# Maduino_Zero_A9G_GPS_Tracker_v3_3.net
KiCad netlist of a schematic drawn in EAGLE
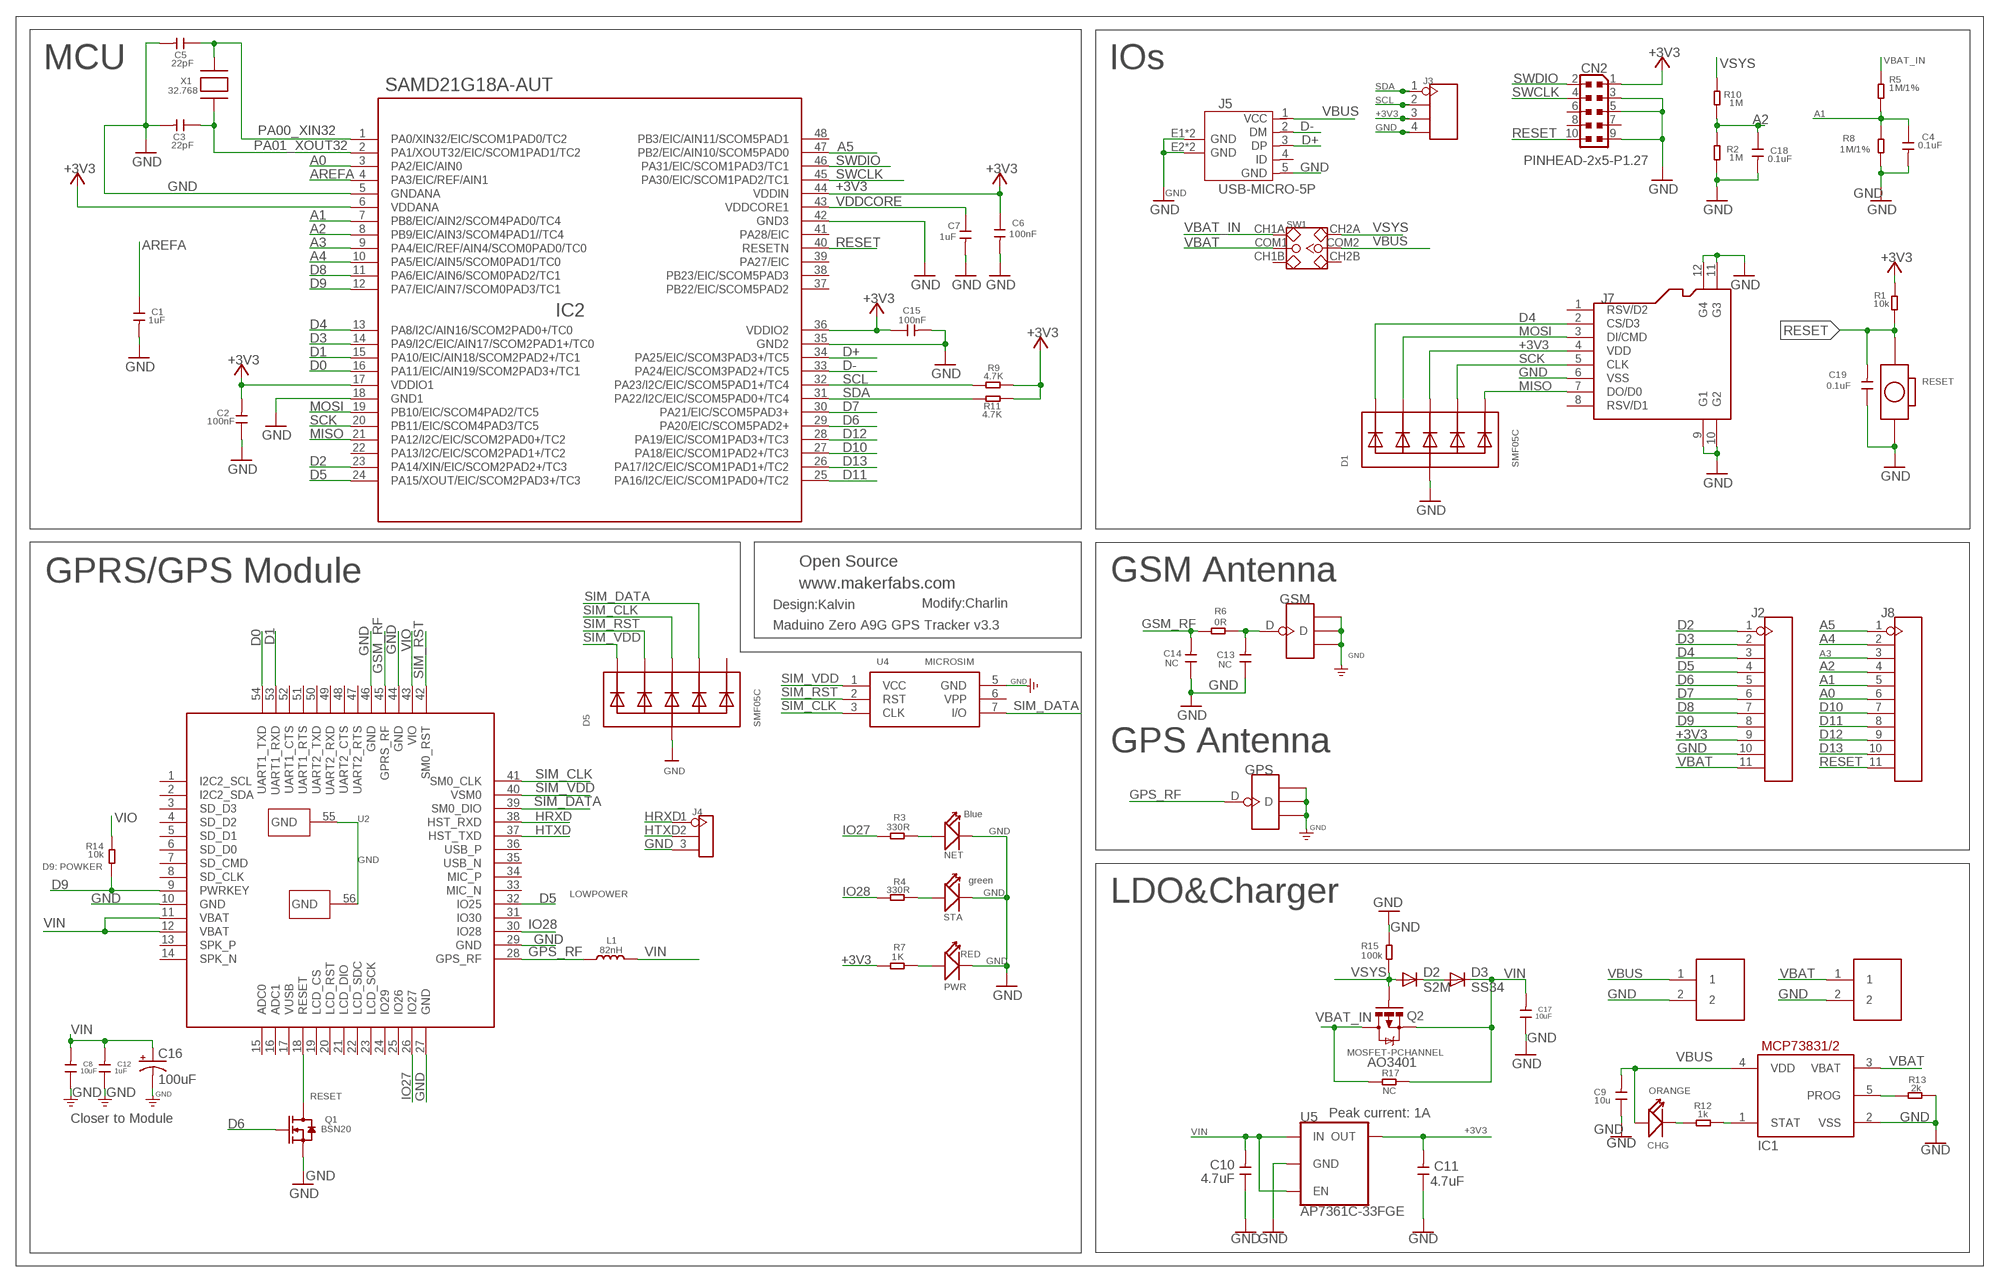
[diagram p0: schematic, sheet 1]

(export (version "E")
  (design (tool "Eeschema 10.0.6"))
  (components
    (comp (ref "C1")
      (value "1uF")
      (footprint "eagle-import:C0603")
      (libsource (lib "eagle-import") (part "C-0603"))
    )
    (comp (ref "C2")
      (value "100nF")
      (footprint "eagle-import:C0603")
      (libsource (lib "eagle-import") (part "C-0603"))
    )
    (comp (ref "C3")
      (value "22pF")
      (footprint "eagle-import:C0603")
      (libsource (lib "eagle-import") (part "C-0603"))
    )
    (comp (ref "C4")
      (value "0.1uF")
      (footprint "eagle-import:C0603")
      (libsource (lib "eagle-import") (part "C-0603"))
    )
    (comp (ref "C5")
      (value "22pF")
      (footprint "eagle-import:C0603")
      (libsource (lib "eagle-import") (part "C-0603"))
    )
    (comp (ref "C6")
      (value "100nF")
      (footprint "eagle-import:C0603")
      (libsource (lib "eagle-import") (part "C-0603"))
    )
    (comp (ref "C7")
      (value "1uF")
      (footprint "eagle-import:C0603")
      (libsource (lib "eagle-import") (part "C-0603"))
    )
    (comp (ref "C8")
      (value "10uF")
      (footprint "eagle-import:C0603")
      (libsource (lib "eagle-import") (part "C-0603"))
    )
    (comp (ref "C9")
      (value "10u")
      (footprint "eagle-import:C0603")
      (libsource (lib "eagle-import") (part "C-0603"))
    )
    (comp (ref "C10")
      (value "4.7uF")
      (footprint "eagle-import:C0603")
      (libsource (lib "eagle-import") (part "C-0603"))
    )
    (comp (ref "C11")
      (value "4.7uF")
      (footprint "eagle-import:C0603")
      (libsource (lib "eagle-import") (part "C-0603"))
    )
    (comp (ref "C12")
      (value "1uF")
      (footprint "eagle-import:C0603")
      (libsource (lib "eagle-import") (part "C-0603"))
    )
    (comp (ref "C13")
      (value "NC")
      (footprint "eagle-import:C0402")
      (libsource (lib "eagle-import") (part "C-0402"))
    )
    (comp (ref "C14")
      (value "NC")
      (footprint "eagle-import:C0402")
      (libsource (lib "eagle-import") (part "C-0402"))
    )
    (comp (ref "C15")
      (value "100nF")
      (footprint "eagle-import:C0603")
      (libsource (lib "eagle-import") (part "C-0603"))
    )
    (comp (ref "C16")
      (value "100uF")
      (footprint "eagle-import:EIA3528")
      (libsource (lib "eagle-import") (part "68UF-POLAR-EIA3528-10V-10%(TANT)"))
    )
    (comp (ref "C17")
      (value "10uF")
      (footprint "eagle-import:C0603")
      (libsource (lib "eagle-import") (part "C-0603"))
    )
    (comp (ref "C18")
      (value "0.1uF")
      (footprint "eagle-import:C0603")
      (libsource (lib "eagle-import") (part "C-0603"))
    )
    (comp (ref "C19")
      (value "0.1uF")
      (footprint "eagle-import:C0603")
      (libsource (lib "eagle-import") (part "C-0603"))
    )
    (comp (ref "CHG")
      (value "ORANGE")
      (footprint "eagle-import:D0603")
      (libsource (lib "eagle-import") (part "007-LED0603"))
    )
    (comp (ref "CN2")
      (value "PINHEAD-2x5-P1.27")
      (footprint "eagle-import:PINHEAD_2X05_127")
      (libsource (lib "eagle-import") (part "0171_PH127-205DF055G00AROUND-PADS"))
    )
    (comp (ref "D1")
      (value "SMF05C")
      (footprint "eagle-import:SOT363")
      (libsource (lib "eagle-import") (part "TVSARRAY_5LANE"))
    )
    (comp (ref "D2")
      (value "S2M")
      (footprint "eagle-import:DO-214AC")
      (libsource (lib "eagle-import") (part "DIODE-DO-214AC"))
    )
    (comp (ref "D3")
      (value "SS34")
      (footprint "eagle-import:DO-214AC")
      (libsource (lib "eagle-import") (part "DIODE-DO-214AC"))
    )
    (comp (ref "D5")
      (value "SMF05C")
      (footprint "eagle-import:SOT363")
      (libsource (lib "eagle-import") (part "TVSARRAY_5LANE"))
    )
    (comp (ref "GPS")
      (value "ANTENNA-U-FL")
      (footprint "eagle-import:4P-U-FL")
      (libsource (lib "eagle-import") (part "ANTENNA-U-FL"))
    )
    (comp (ref "GSM")
      (value "ANTENNA-U-FL")
      (footprint "eagle-import:4P-U-FL")
      (libsource (lib "eagle-import") (part "ANTENNA-U-FL"))
    )
    (comp (ref "IC1")
      (value "MCP73831/OT")
      (footprint "eagle-import:SOT23-5L")
      (libsource (lib "eagle-import") (part "MCP73831/OT"))
    )
    (comp (ref "IC2")
      (value "SAMD21G18A-AUT")
      (footprint "eagle-import:TQFP48-7X7")
      (libsource (lib "eagle-import") (part "ATSAMD21G18A-AUT"))
    )
    (comp (ref "J1")
      (value "PH2.0-2P-90-DIP")
      (footprint "eagle-import:PH2.0-2P-90-DIP")
      (libsource (lib "eagle-import") (part "PH2.0-2P-90-DIP"))
    )
    (comp (ref "J2")
      (value "HEADER-11P-2.54")
      (footprint "eagle-import:11P-2.54")
      (libsource (lib "eagle-import") (part "HEADER-11P-2.54"))
    )
    (comp (ref "J3")
      (value "HEADER-4P-60/35MILROUND")
      (footprint "eagle-import:4P-65_35ROUND")
      (libsource (lib "eagle-import") (part "HEADER-4P-60/35MILROUND"))
    )
    (comp (ref "J4")
      (value "HEADER-3P-2.54")
      (footprint "eagle-import:3P-2.54")
      (libsource (lib "eagle-import") (part "HEADER-3P-2.54"))
    )
    (comp (ref "J5")
      (value "USB-MICRO-5P")
      (footprint "eagle-import:MICRO-USB-5P")
      (libsource (lib "eagle-import") (part "USB-MICRO-5P"))
    )
    (comp (ref "J6")
      (value "PH2.0-2P-90-DIP")
      (footprint "eagle-import:PH2.0-2P-90-DIP")
      (libsource (lib "eagle-import") (part "PH2.0-2P-90-DIP"))
    )
    (comp (ref "J7")
      (value "HOLDER-MICROSD-8P")
      (footprint "eagle-import:8P-SMD")
      (libsource (lib "eagle-import") (part "HOLDER-MICROSD-8P"))
    )
    (comp (ref "J8")
      (value "HEADER-11P-2.54")
      (footprint "eagle-import:11P-2.54")
      (libsource (lib "eagle-import") (part "HEADER-11P-2.54"))
    )
    (comp (ref "L1")
      (value "82nH")
      (footprint "eagle-import:L0603")
      (libsource (lib "eagle-import") (part "L'0603'"))
    )
    (comp (ref "NET")
      (value "Blue")
      (footprint "eagle-import:LED-0603")
      (libsource (lib "eagle-import") (part "LED'0603'"))
    )
    (comp (ref "PWR")
      (value "RED")
      (footprint "eagle-import:LED-0603")
      (libsource (lib "eagle-import") (part "LED'0603'"))
    )
    (comp (ref "Q1")
      (value "BSN20")
      (footprint "eagle-import:SOT23@1")
      (libsource (lib "eagle-import") (part "MOSFET-N'SOT23'"))
    )
    (comp (ref "Q2")
      (value "MOSFET-PCHANNEL")
      (footprint "eagle-import:SOT23-3")
      (libsource (lib "eagle-import") (part "MOSFET-PCHANNEL"))
    )
    (comp (ref "R1")
      (value "10k")
      (footprint "eagle-import:R0603")
      (libsource (lib "eagle-import") (part "R-0603"))
    )
    (comp (ref "R2")
      (value "1M")
      (footprint "eagle-import:R0603")
      (libsource (lib "eagle-import") (part "R-0603"))
    )
    (comp (ref "R3")
      (value "330R")
      (footprint "eagle-import:R0603")
      (libsource (lib "eagle-import") (part "R-0603"))
    )
    (comp (ref "R4")
      (value "330R")
      (footprint "eagle-import:R0603")
      (libsource (lib "eagle-import") (part "R-0603"))
    )
    (comp (ref "R5")
      (value "1M/1%")
      (footprint "eagle-import:R0603")
      (libsource (lib "eagle-import") (part "R-0603"))
    )
    (comp (ref "R6")
      (value "0R")
      (footprint "eagle-import:R0603")
      (libsource (lib "eagle-import") (part "R-0603"))
    )
    (comp (ref "R7")
      (value "1K")
      (footprint "eagle-import:R0603")
      (libsource (lib "eagle-import") (part "R-0603"))
    )
    (comp (ref "R8")
      (value "1M/1%")
      (footprint "eagle-import:R0603")
      (libsource (lib "eagle-import") (part "R-0603"))
    )
    (comp (ref "R9")
      (value "4.7K")
      (footprint "eagle-import:R0603")
      (libsource (lib "eagle-import") (part "R-0603"))
    )
    (comp (ref "R10")
      (value "1M")
      (footprint "eagle-import:R0603")
      (libsource (lib "eagle-import") (part "R-0603"))
    )
    (comp (ref "R11")
      (value "4.7K")
      (footprint "eagle-import:R0603")
      (libsource (lib "eagle-import") (part "R-0603"))
    )
    (comp (ref "R12")
      (value "1k")
      (footprint "eagle-import:R0603")
      (libsource (lib "eagle-import") (part "R-0603"))
    )
    (comp (ref "R13")
      (value "2k")
      (footprint "eagle-import:R0603")
      (libsource (lib "eagle-import") (part "R-0603"))
    )
    (comp (ref "R14")
      (value "10k")
      (footprint "eagle-import:R0603")
      (libsource (lib "eagle-import") (part "R-0603"))
    )
    (comp (ref "R15")
      (value "100k")
      (footprint "eagle-import:R0603")
      (libsource (lib "eagle-import") (part "R-0603"))
    )
    (comp (ref "R17")
      (value "NC")
      (footprint "eagle-import:R0603")
      (libsource (lib "eagle-import") (part "R-0603"))
    )
    (comp (ref "RESET")
      (value "BOTTON-2P-90D")
      (footprint "eagle-import:2P-7.62X3.56-90D")
      (libsource (lib "eagle-import") (part "BOTTON-2P-90D"))
    )
    (comp (ref "STA")
      (value "green")
      (footprint "eagle-import:LED-0603")
      (libsource (lib "eagle-import") (part "LED'0603'"))
    )
    (comp (ref "SW1")
      (value "SWITCH-2CH-6P")
      (footprint "eagle-import:6P-2CH-2.54-7.6X3.0")
      (libsource (lib "eagle-import") (part "SWITCH-2CH-6P"))
    )
    (comp (ref "U2")
      (value "A9G")
      (footprint "eagle-import:A9G")
      (libsource (lib "eagle-import") (part "A9G"))
    )
    (comp (ref "U4")
      (value "MICROSIM")
      (footprint "eagle-import:MICROSIM")
      (libsource (lib "eagle-import") (part "MICROSIM"))
    )
    (comp (ref "U5")
      (value "AP7361C-33FGE")
      (footprint "eagle-import:8-UDFN")
      (libsource (lib "eagle-import") (part "AP7361C-33FGE"))
    )
    (comp (ref "X1")
      (value "32.768")
      (footprint "eagle-import:XTAL3215")
      (libsource (lib "eagle-import") (part "XTAL-3.2X1.5"))
    )
  )
  (nets
    (net (code "1") (name "+3V3") (class "Default")
      (node (ref "C11") (pin "2") (pinfunction "2_2") (pintype "passive"))
      (node (ref "C15") (pin "1") (pinfunction "1_1") (pintype "passive"))
      (node (ref "C2") (pin "2") (pinfunction "2_2") (pintype "passive"))
      (node (ref "C6") (pin "1") (pinfunction "1_1") (pintype "passive"))
      (node (ref "CN2") (pin "1") (pinfunction "1_1") (pintype "passive"))
      (node (ref "D1") (pin "4") (pinfunction "C3_4") (pintype "passive"))
      (node (ref "IC2") (pin "17") (pinfunction "VDDIO1_17") (pintype "power_in"))
      (node (ref "IC2") (pin "36") (pinfunction "VDDIO2_36") (pintype "power_in"))
      (node (ref "IC2") (pin "44") (pinfunction "VDDIN_44") (pintype "power_in"))
      (node (ref "IC2") (pin "6") (pinfunction "VDDANA_6") (pintype "power_in"))
      (node (ref "J2") (pin "9") (pinfunction "9_9") (pintype "bidirectional"))
      (node (ref "J3") (pin "3") (pinfunction "P$3_3") (pintype "bidirectional"))
      (node (ref "J7") (pin "4") (pinfunction "VDD_4") (pintype "bidirectional"))
      (node (ref "R1") (pin "2") (pinfunction "2_2") (pintype "passive"))
      (node (ref "R11") (pin "2") (pinfunction "2_2") (pintype "passive"))
      (node (ref "R7") (pin "1") (pinfunction "1_1") (pintype "passive"))
      (node (ref "R9") (pin "2") (pinfunction "2_2") (pintype "passive"))
      (node (ref "U5") (pin "1") (pinfunction "OUT_1") (pintype "output"))
    )
    (net (code "2") (name "/A0") (class "Default")
      (node (ref "IC2") (pin "3") (pinfunction "PA2/EIC/AIN0_3") (pintype "bidirectional"))
      (node (ref "J8") (pin "6") (pinfunction "6_6") (pintype "bidirectional"))
    )
    (net (code "3") (name "/A1") (class "Default")
      (node (ref "C4") (pin "1") (pinfunction "1_1") (pintype "passive"))
      (node (ref "IC2") (pin "7") (pinfunction "PB8/EIC/AIN2/SCOM4PAD0/TC4_7") (pintype "bidirectional"))
      (node (ref "J8") (pin "5") (pinfunction "5_5") (pintype "bidirectional"))
      (node (ref "R5") (pin "1") (pinfunction "1_1") (pintype "passive"))
      (node (ref "R8") (pin "2") (pinfunction "2_2") (pintype "passive"))
    )
    (net (code "4") (name "/A2") (class "Default")
      (node (ref "C18") (pin "1") (pinfunction "1_1") (pintype "passive"))
      (node (ref "IC2") (pin "8") (pinfunction "PB9/EIC/AIN3/SCOM4PAD1//TC4_8") (pintype "bidirectional"))
      (node (ref "J8") (pin "4") (pinfunction "4_4") (pintype "bidirectional"))
      (node (ref "R10") (pin "1") (pinfunction "1_1") (pintype "passive"))
      (node (ref "R2") (pin "2") (pinfunction "2_2") (pintype "passive"))
    )
    (net (code "5") (name "/A3") (class "Default")
      (node (ref "IC2") (pin "9") (pinfunction "PA4/EIC/REF/AIN4/SCOM0PAD0/TC0_9") (pintype "bidirectional"))
      (node (ref "J8") (pin "3") (pinfunction "3_3") (pintype "bidirectional"))
    )
    (net (code "6") (name "/A4") (class "Default")
      (node (ref "IC2") (pin "10") (pinfunction "PA5/EIC/AIN5/SCOM0PAD1/TC0_10") (pintype "bidirectional"))
      (node (ref "J8") (pin "2") (pinfunction "2_2") (pintype "bidirectional"))
    )
    (net (code "7") (name "/A5") (class "Default")
      (node (ref "IC2") (pin "47") (pinfunction "PB2/EIC/AIN10/SCOM5PAD0_47") (pintype "bidirectional"))
      (node (ref "J8") (pin "1") (pinfunction "1_1") (pintype "bidirectional"))
    )
    (net (code "8") (name "/AREFA") (class "Default")
      (node (ref "C1") (pin "1") (pinfunction "1_1") (pintype "passive"))
      (node (ref "IC2") (pin "4") (pinfunction "PA3/EIC/REF/AIN1_4") (pintype "bidirectional"))
    )
    (net (code "9") (name "/D+") (class "Default")
      (node (ref "IC2") (pin "34") (pinfunction "PA25/EIC/SCOM3PAD3+/TC5_34") (pintype "bidirectional"))
      (node (ref "J5") (pin "3") (pinfunction "DP_3") (pintype "bidirectional"))
    )
    (net (code "10") (name "/D-") (class "Default")
      (node (ref "IC2") (pin "33") (pinfunction "PA24/EIC/SCOM3PAD2+/TC5_33") (pintype "bidirectional"))
      (node (ref "J5") (pin "2") (pinfunction "DM_2") (pintype "bidirectional"))
    )
    (net (code "11") (name "/D0") (class "Default")
      (node (ref "IC2") (pin "16") (pinfunction "PA11/EIC/AIN19/SCOM2PAD3+/TC1_16") (pintype "bidirectional"))
      (node (ref "U2") (pin "54") (pinfunction "UART1_TXD_54") (pintype "bidirectional"))
    )
    (net (code "12") (name "/D1") (class "Default")
      (node (ref "IC2") (pin "15") (pinfunction "PA10/EIC/AIN18/SCOM2PAD2+/TC1_15") (pintype "bidirectional"))
      (node (ref "U2") (pin "53") (pinfunction "UART1_RXD_53") (pintype "bidirectional"))
    )
    (net (code "13") (name "/D2") (class "Default")
      (node (ref "IC2") (pin "23") (pinfunction "PA14/XIN/EIC/SCOM2PAD2+/TC3_23") (pintype "bidirectional"))
      (node (ref "J2") (pin "1") (pinfunction "1_1") (pintype "bidirectional"))
    )
    (net (code "14") (name "/D3") (class "Default")
      (node (ref "IC2") (pin "14") (pinfunction "PA9/I2C/EIC/AIN17/SCOM2PAD1+/TC0_14") (pintype "bidirectional"))
      (node (ref "J2") (pin "2") (pinfunction "2_2") (pintype "bidirectional"))
    )
    (net (code "15") (name "/D4") (class "Default")
      (node (ref "D1") (pin "1") (pinfunction "C1_1") (pintype "passive"))
      (node (ref "IC2") (pin "13") (pinfunction "PA8/I2C/AIN16/SCOM2PAD0+/TC0_13") (pintype "bidirectional"))
      (node (ref "J2") (pin "3") (pinfunction "3_3") (pintype "bidirectional"))
      (node (ref "J7") (pin "2") (pinfunction "CS/D3_2") (pintype "bidirectional"))
    )
    (net (code "16") (name "/D5") (class "Default")
      (node (ref "IC2") (pin "24") (pinfunction "PA15/XOUT/EIC/SCOM2PAD3+/TC3_24") (pintype "bidirectional"))
      (node (ref "J2") (pin "4") (pinfunction "4_4") (pintype "bidirectional"))
      (node (ref "U2") (pin "32") (pinfunction "IO25_32") (pintype "bidirectional"))
    )
    (net (code "17") (name "/D6") (class "Default")
      (node (ref "IC2") (pin "29") (pinfunction "PA20/EIC/SCOM5PAD2+_29") (pintype "bidirectional"))
      (node (ref "J2") (pin "5") (pinfunction "5_5") (pintype "bidirectional"))
      (node (ref "Q1") (pin "1") (pinfunction "G_1") (pintype "passive"))
    )
    (net (code "18") (name "/D7") (class "Default")
      (node (ref "IC2") (pin "30") (pinfunction "PA21/EIC/SCOM5PAD3+_30") (pintype "bidirectional"))
      (node (ref "J2") (pin "6") (pinfunction "6_6") (pintype "bidirectional"))
    )
    (net (code "19") (name "/D8") (class "Default")
      (node (ref "IC2") (pin "11") (pinfunction "PA6/EIC/AIN6/SCOM0PAD2/TC1_11") (pintype "bidirectional"))
      (node (ref "J2") (pin "7") (pinfunction "7_7") (pintype "bidirectional"))
    )
    (net (code "20") (name "/D9") (class "Default")
      (node (ref "IC2") (pin "12") (pinfunction "PA7/EIC/AIN7/SCOM0PAD3/TC1_12") (pintype "bidirectional"))
      (node (ref "J2") (pin "8") (pinfunction "8_8") (pintype "bidirectional"))
      (node (ref "R14") (pin "1") (pinfunction "1_1") (pintype "passive"))
      (node (ref "U2") (pin "9") (pinfunction "PWRKEY_9") (pintype "bidirectional"))
    )
    (net (code "21") (name "/D10") (class "Default")
      (node (ref "IC2") (pin "27") (pinfunction "PA18/EIC/SCOM1PAD2+/TC3_27") (pintype "bidirectional"))
      (node (ref "J8") (pin "7") (pinfunction "7_7") (pintype "bidirectional"))
    )
    (net (code "22") (name "/D11") (class "Default")
      (node (ref "IC2") (pin "25") (pinfunction "PA16/I2C/EIC/SCOM1PAD0+/TC2_25") (pintype "bidirectional"))
      (node (ref "J8") (pin "8") (pinfunction "8_8") (pintype "bidirectional"))
    )
    (net (code "23") (name "/D12") (class "Default")
      (node (ref "IC2") (pin "28") (pinfunction "PA19/EIC/SCOM1PAD3+/TC3_28") (pintype "bidirectional"))
      (node (ref "J8") (pin "9") (pinfunction "9_9") (pintype "bidirectional"))
    )
    (net (code "24") (name "/D13") (class "Default")
      (node (ref "IC2") (pin "26") (pinfunction "PA17/I2C/EIC/SCOM1PAD1+/TC2_26") (pintype "bidirectional"))
      (node (ref "J8") (pin "10") (pinfunction "10_10") (pintype "bidirectional"))
    )
    (net (code "25") (name "/GPS_RF") (class "Default")
      (node (ref "GPS") (pin "D") (pinfunction "D_D") (pintype "bidirectional"))
      (node (ref "L1") (pin "1") (pinfunction "1_1") (pintype "passive"))
      (node (ref "U2") (pin "28") (pinfunction "GPS_RF_28") (pintype "bidirectional"))
    )
    (net (code "26") (name "/GSM_RF") (class "Default")
      (node (ref "C14") (pin "2") (pinfunction "2_2") (pintype "passive"))
      (node (ref "R6") (pin "1") (pinfunction "1_1") (pintype "passive"))
      (node (ref "U2") (pin "45") (pinfunction "GPRS_RF_45") (pintype "bidirectional"))
    )
    (net (code "27") (name "/HRXD") (class "Default")
      (node (ref "J4") (pin "1") (pinfunction "P$1_1") (pintype "bidirectional"))
      (node (ref "U2") (pin "38") (pinfunction "HST_RXD_38") (pintype "bidirectional"))
    )
    (net (code "28") (name "/HTXD") (class "Default")
      (node (ref "J4") (pin "2") (pinfunction "P$2_2") (pintype "bidirectional"))
      (node (ref "U2") (pin "37") (pinfunction "HST_TXD_37") (pintype "bidirectional"))
    )
    (net (code "29") (name "/IO27") (class "Default")
      (node (ref "R3") (pin "1") (pinfunction "1_1") (pintype "passive"))
      (node (ref "U2") (pin "26") (pinfunction "IO27_26") (pintype "bidirectional"))
    )
    (net (code "30") (name "/IO28") (class "Default")
      (node (ref "R4") (pin "1") (pinfunction "1_1") (pintype "passive"))
      (node (ref "U2") (pin "30") (pinfunction "IO28_30") (pintype "bidirectional"))
    )
    (net (code "31") (name "/MISO") (class "Default")
      (node (ref "D1") (pin "6") (pinfunction "C5_6") (pintype "passive"))
      (node (ref "IC2") (pin "21") (pinfunction "PA12/I2C/EIC/SCOM2PAD0+/TC2_21") (pintype "bidirectional"))
      (node (ref "J7") (pin "7") (pinfunction "DO/D0_7") (pintype "bidirectional"))
    )
    (net (code "32") (name "/MOSI") (class "Default")
      (node (ref "D1") (pin "3") (pinfunction "C2_3") (pintype "passive"))
      (node (ref "IC2") (pin "19") (pinfunction "PB10/EIC/SCOM4PAD2/TC5_19") (pintype "bidirectional"))
      (node (ref "J7") (pin "3") (pinfunction "DI/CMD_3") (pintype "bidirectional"))
    )
    (net (code "33") (name "/PA00_XIN32") (class "Default")
      (node (ref "C5") (pin "1") (pinfunction "1_1") (pintype "passive"))
      (node (ref "IC2") (pin "1") (pinfunction "PA0/XIN32/EIC/SCOM1PAD0/TC2_1") (pintype "bidirectional"))
      (node (ref "X1") (pin "P$2") (pinfunction "P$2_P$2") (pintype "bidirectional"))
    )
    (net (code "34") (name "/PA01_XOUT32") (class "Default")
      (node (ref "C3") (pin "1") (pinfunction "1_1") (pintype "passive"))
      (node (ref "IC2") (pin "2") (pinfunction "PA1/XOUT32/EIC/SCOM1PAD1/TC2_2") (pintype "bidirectional"))
      (node (ref "X1") (pin "P$1") (pinfunction "P$1_P$1") (pintype "bidirectional"))
    )
    (net (code "35") (name "/SCK") (class "Default")
      (node (ref "D1") (pin "5") (pinfunction "C4_5") (pintype "passive"))
      (node (ref "IC2") (pin "20") (pinfunction "PB11/EIC/SCOM4PAD3/TC5_20") (pintype "bidirectional"))
      (node (ref "J7") (pin "5") (pinfunction "CLK_5") (pintype "bidirectional"))
    )
    (net (code "36") (name "/SCL") (class "Default")
      (node (ref "IC2") (pin "32") (pinfunction "PA23/I2C/EIC/SCOM5PAD1+/TC4_32") (pintype "bidirectional"))
      (node (ref "J3") (pin "2") (pinfunction "P$2_2") (pintype "bidirectional"))
      (node (ref "R9") (pin "1") (pinfunction "1_1") (pintype "passive"))
    )
    (net (code "37") (name "/SDA") (class "Default")
      (node (ref "IC2") (pin "31") (pinfunction "PA22/I2C/EIC/SCOM5PAD0+/TC4_31") (pintype "bidirectional"))
      (node (ref "J3") (pin "1") (pinfunction "P$1_1") (pintype "bidirectional"))
      (node (ref "R11") (pin "1") (pinfunction "1_1") (pintype "passive"))
    )
    (net (code "38") (name "/SIM_CLK") (class "Default")
      (node (ref "D5") (pin "4") (pinfunction "C3_4") (pintype "passive"))
      (node (ref "U2") (pin "41") (pinfunction "SM0_CLK_41") (pintype "bidirectional"))
      (node (ref "U4") (pin "3") (pinfunction "CLK_3") (pintype "bidirectional"))
    )
    (net (code "39") (name "/SIM_DATA") (class "Default")
      (node (ref "D5") (pin "5") (pinfunction "C4_5") (pintype "passive"))
      (node (ref "U2") (pin "39") (pinfunction "SM0_DIO_39") (pintype "bidirectional"))
      (node (ref "U4") (pin "7") (pinfunction "I/O_7") (pintype "bidirectional"))
    )
    (net (code "40") (name "/SIM_RST") (class "Default")
      (node (ref "D5") (pin "3") (pinfunction "C2_3") (pintype "passive"))
      (node (ref "U2") (pin "42") (pinfunction "SM0_RST_42") (pintype "bidirectional"))
      (node (ref "U4") (pin "2") (pinfunction "RST_2") (pintype "bidirectional"))
    )
    (net (code "41") (name "/SIM_VDD") (class "Default")
      (node (ref "D5") (pin "1") (pinfunction "C1_1") (pintype "passive"))
      (node (ref "U2") (pin "40") (pinfunction "VSM0_40") (pintype "bidirectional"))
      (node (ref "U4") (pin "1") (pinfunction "VCC_1") (pintype "bidirectional"))
    )
    (net (code "42") (name "/SWCLK") (class "Default")
      (node (ref "CN2") (pin "4") (pinfunction "4_4") (pintype "passive"))
      (node (ref "IC2") (pin "45") (pinfunction "PA30/EIC/SCOM1PAD2/TC1_45") (pintype "bidirectional"))
    )
    (net (code "43") (name "/SWDIO") (class "Default")
      (node (ref "CN2") (pin "2") (pinfunction "2_2") (pintype "passive"))
      (node (ref "IC2") (pin "46") (pinfunction "PA31/EIC/SCOM1PAD3/TC1_46") (pintype "bidirectional"))
    )
    (net (code "44") (name "/VBAT") (class "Default")
      (node (ref "IC1") (pin "3") (pinfunction "VBAT_3") (pintype "bidirectional"))
      (node (ref "J2") (pin "11") (pinfunction "11_11") (pintype "bidirectional"))
      (node (ref "J6") (pin "1") (pinfunction "1_1") (pintype "bidirectional"))
      (node (ref "SW1") (pin "COM1") (pinfunction "COM1_COM1") (pintype "bidirectional"))
    )
    (net (code "45") (name "/VBAT_IN") (class "Default")
      (node (ref "Q2") (pin "3") (pinfunction "D_3") (pintype "passive"))
      (node (ref "R17") (pin "1") (pinfunction "1_1") (pintype "passive"))
      (node (ref "R5") (pin "2") (pinfunction "2_2") (pintype "passive"))
      (node (ref "SW1") (pin "CH1A") (pinfunction "CH1A_CH1A") (pintype "bidirectional"))
    )
    (net (code "46") (name "/VBUS") (class "Default")
      (node (ref "C9") (pin "2") (pinfunction "2_2") (pintype "passive"))
      (node (ref "CHG") (pin "+") (pinfunction "+_+") (pintype "passive"))
      (node (ref "IC1") (pin "4") (pinfunction "VDD_4") (pintype "power_in"))
      (node (ref "J1") (pin "1") (pinfunction "1_1") (pintype "bidirectional"))
      (node (ref "J5") (pin "1") (pinfunction "VCC_1") (pintype "bidirectional"))
      (node (ref "SW1") (pin "COM2") (pinfunction "COM2_COM2") (pintype "bidirectional"))
    )
    (net (code "47") (name "/VDDCORE") (class "Default")
      (node (ref "C7") (pin "1") (pinfunction "1_1") (pintype "passive"))
      (node (ref "IC2") (pin "43") (pinfunction "VDDCORE1_43") (pintype "input"))
    )
    (net (code "48") (name "/VIN") (class "Default")
      (node (ref "C10") (pin "2") (pinfunction "2_2") (pintype "passive"))
      (node (ref "C12") (pin "2") (pinfunction "2_2") (pintype "passive"))
      (node (ref "C16") (pin "A") (pinfunction "+_A") (pintype "passive"))
      (node (ref "C17") (pin "2") (pinfunction "2_2") (pintype "passive"))
      (node (ref "C8") (pin "2") (pinfunction "2_2") (pintype "passive"))
      (node (ref "D3") (pin "C") (pinfunction "C_C") (pintype "passive"))
      (node (ref "L1") (pin "2") (pinfunction "2_2") (pintype "passive"))
      (node (ref "Q2") (pin "2") (pinfunction "S_2") (pintype "passive"))
      (node (ref "R17") (pin "2") (pinfunction "2_2") (pintype "passive"))
      (node (ref "U2") (pin "11") (pinfunction "VBAT_11") (pintype "bidirectional"))
      (node (ref "U2") (pin "12") (pinfunction "VBAT_12") (pintype "bidirectional"))
      (node (ref "U5") (pin "5") (pinfunction "EN_5") (pintype "bidirectional"))
      (node (ref "U5") (pin "8") (pinfunction "IN_8") (pintype "input"))
    )
    (net (code "49") (name "/VIO") (class "Default")
      (node (ref "R14") (pin "2") (pinfunction "2_2") (pintype "passive"))
      (node (ref "U2") (pin "43") (pinfunction "VIO_43") (pintype "bidirectional"))
    )
    (net (code "50") (name "/VSYS") (class "Default")
      (node (ref "D2") (pin "A") (pinfunction "A_A") (pintype "passive"))
      (node (ref "Q2") (pin "1") (pinfunction "G_1") (pintype "passive"))
      (node (ref "R10") (pin "2") (pinfunction "2_2") (pintype "passive"))
      (node (ref "R15") (pin "1") (pinfunction "1_1") (pintype "passive"))
      (node (ref "SW1") (pin "CH2A") (pinfunction "CH2A_CH2A") (pintype "bidirectional"))
    )
    (net (code "51") (name "GND") (class "Default")
      (node (ref "C1") (pin "2") (pinfunction "2_2") (pintype "passive"))
      (node (ref "C10") (pin "1") (pinfunction "1_1") (pintype "passive"))
      (node (ref "C11") (pin "1") (pinfunction "1_1") (pintype "passive"))
      (node (ref "C12") (pin "1") (pinfunction "1_1") (pintype "passive"))
      (node (ref "C13") (pin "1") (pinfunction "1_1") (pintype "passive"))
      (node (ref "C14") (pin "1") (pinfunction "1_1") (pintype "passive"))
      (node (ref "C15") (pin "2") (pinfunction "2_2") (pintype "passive"))
      (node (ref "C16") (pin "C") (pinfunction "-_C") (pintype "passive"))
      (node (ref "C17") (pin "1") (pinfunction "1_1") (pintype "passive"))
      (node (ref "C18") (pin "2") (pinfunction "2_2") (pintype "passive"))
      (node (ref "C19") (pin "1") (pinfunction "1_1") (pintype "passive"))
      (node (ref "C2") (pin "1") (pinfunction "1_1") (pintype "passive"))
      (node (ref "C3") (pin "2") (pinfunction "2_2") (pintype "passive"))
      (node (ref "C4") (pin "2") (pinfunction "2_2") (pintype "passive"))
      (node (ref "C5") (pin "2") (pinfunction "2_2") (pintype "passive"))
      (node (ref "C6") (pin "2") (pinfunction "2_2") (pintype "passive"))
      (node (ref "C7") (pin "2") (pinfunction "2_2") (pintype "passive"))
      (node (ref "C8") (pin "1") (pinfunction "1_1") (pintype "passive"))
      (node (ref "C9") (pin "1") (pinfunction "1_1") (pintype "passive"))
      (node (ref "CN2") (pin "3") (pinfunction "3_3") (pintype "passive"))
      (node (ref "CN2") (pin "5") (pinfunction "5_5") (pintype "passive"))
      (node (ref "CN2") (pin "9") (pinfunction "9_9") (pintype "passive"))
      (node (ref "D1") (pin "2") (pinfunction "A_2") (pintype "passive"))
      (node (ref "D5") (pin "2") (pinfunction "A_2") (pintype "passive"))
      (node (ref "GPS") (pin "GND1") (pinfunction "GND1_GND1") (pintype "bidirectional"))
      (node (ref "GPS") (pin "GND2") (pinfunction "GND2_GND2") (pintype "bidirectional"))
      (node (ref "GPS") (pin "GND3") (pinfunction "GND3_GND3") (pintype "bidirectional"))
      (node (ref "GSM") (pin "GND1") (pinfunction "GND1_GND1") (pintype "bidirectional"))
      (node (ref "GSM") (pin "GND2") (pinfunction "GND2_GND2") (pintype "bidirectional"))
      (node (ref "GSM") (pin "GND3") (pinfunction "GND3_GND3") (pintype "bidirectional"))
      (node (ref "IC1") (pin "2") (pinfunction "VSS_2") (pintype "power_in"))
      (node (ref "IC2") (pin "18") (pinfunction "GND1_18") (pintype "power_in"))
      (node (ref "IC2") (pin "35") (pinfunction "GND2_35") (pintype "power_in"))
      (node (ref "IC2") (pin "42") (pinfunction "GND3_42") (pintype "power_in"))
      (node (ref "IC2") (pin "5") (pinfunction "GNDANA_5") (pintype "power_in"))
      (node (ref "J1") (pin "2") (pinfunction "2_2") (pintype "bidirectional"))
      (node (ref "J2") (pin "10") (pinfunction "10_10") (pintype "bidirectional"))
      (node (ref "J3") (pin "4") (pinfunction "P$4_4") (pintype "bidirectional"))
      (node (ref "J4") (pin "3") (pinfunction "P$3_3") (pintype "bidirectional"))
      (node (ref "J5") (pin "5") (pinfunction "GND_5") (pintype "bidirectional"))
      (node (ref "J5") (pin "E1") (pinfunction "GND_E1") (pintype "bidirectional"))
      (node (ref "J5") (pin "E2") (pinfunction "GND_E2") (pintype "bidirectional"))
      (node (ref "J5") (pin "P1") (pinfunction "GND_P1") (pintype "bidirectional"))
      (node (ref "J5") (pin "P2") (pinfunction "GND_P2") (pintype "bidirectional"))
      (node (ref "J6") (pin "2") (pinfunction "2_2") (pintype "bidirectional"))
      (node (ref "J7") (pin "10") (pinfunction "G2_10") (pintype "bidirectional"))
      (node (ref "J7") (pin "11") (pinfunction "G3_11") (pintype "bidirectional"))
      (node (ref "J7") (pin "12") (pinfunction "G4_12") (pintype "bidirectional"))
      (node (ref "J7") (pin "6") (pinfunction "VSS_6") (pintype "bidirectional"))
      (node (ref "J7") (pin "9") (pinfunction "G1_9") (pintype "bidirectional"))
      (node (ref "NET") (pin "-") (pinfunction "-_-") (pintype "passive"))
      (node (ref "PWR") (pin "-") (pinfunction "-_-") (pintype "passive"))
      (node (ref "Q1") (pin "2") (pinfunction "S_2") (pintype "passive"))
      (node (ref "R13") (pin "2") (pinfunction "2_2") (pintype "passive"))
      (node (ref "R15") (pin "2") (pinfunction "2_2") (pintype "passive"))
      (node (ref "R2") (pin "1") (pinfunction "1_1") (pintype "passive"))
      (node (ref "R8") (pin "1") (pinfunction "1_1") (pintype "passive"))
      (node (ref "RESET") (pin "P$2") (pinfunction "2_P$2") (pintype "bidirectional"))
      (node (ref "STA") (pin "-") (pinfunction "-_-") (pintype "passive"))
      (node (ref "U2") (pin "10") (pinfunction "GND_10") (pintype "bidirectional"))
      (node (ref "U2") (pin "27") (pinfunction "GND_27") (pintype "bidirectional"))
      (node (ref "U2") (pin "29") (pinfunction "GND_29") (pintype "bidirectional"))
      (node (ref "U2") (pin "44") (pinfunction "GND_44") (pintype "bidirectional"))
      (node (ref "U2") (pin "46") (pinfunction "GND_46") (pintype "bidirectional"))
      (node (ref "U2") (pin "55") (pinfunction "GND_55") (pintype "bidirectional"))
      (node (ref "U2") (pin "56") (pinfunction "GND_56") (pintype "bidirectional"))
      (node (ref "U4") (pin "5") (pinfunction "GND_5") (pintype "bidirectional"))
      (node (ref "U5") (pin "4") (pinfunction "GND_4") (pintype "input"))
      (node (ref "U5") (pin "EP") (pinfunction "GND_EP") (pintype "input"))
    )
    (net (code "52") (name "Net-(C13-Pad2)") (class "Default")
      (node (ref "C13") (pin "2") (pinfunction "2_2") (pintype "passive"))
      (node (ref "GSM") (pin "D") (pinfunction "D_D") (pintype "bidirectional"))
      (node (ref "R6") (pin "2") (pinfunction "2_2") (pintype "passive"))
    )
    (net (code "53") (name "Net-(CHG-Pad-)") (class "Default")
      (node (ref "CHG") (pin "-") (pinfunction "-_-") (pintype "passive"))
      (node (ref "R12") (pin "1") (pinfunction "1_1") (pintype "passive"))
    )
    (net (code "54") (name "Net-(D2-PadC)") (class "Default")
      (node (ref "D2") (pin "C") (pinfunction "C_C") (pintype "passive"))
      (node (ref "D3") (pin "A") (pinfunction "A_A") (pintype "passive"))
    )
    (net (code "55") (name "Net-(IC1-PROG)") (class "Default")
      (node (ref "IC1") (pin "5") (pinfunction "PROG_5") (pintype "input"))
      (node (ref "R13") (pin "1") (pinfunction "1_1") (pintype "passive"))
    )
    (net (code "56") (name "Net-(IC1-STAT)") (class "Default")
      (node (ref "IC1") (pin "1") (pinfunction "STAT_1") (pintype "output"))
      (node (ref "R12") (pin "2") (pinfunction "2_2") (pintype "passive"))
    )
    (net (code "57") (name "Net-(NET-Pad+)") (class "Default")
      (node (ref "NET") (pin "+") (pinfunction "+_+") (pintype "passive"))
      (node (ref "R3") (pin "2") (pinfunction "2_2") (pintype "passive"))
    )
    (net (code "58") (name "Net-(PWR-Pad+)") (class "Default")
      (node (ref "PWR") (pin "+") (pinfunction "+_+") (pintype "passive"))
      (node (ref "R7") (pin "2") (pinfunction "2_2") (pintype "passive"))
    )
    (net (code "59") (name "Net-(Q1-D)") (class "Default")
      (node (ref "Q1") (pin "3") (pinfunction "D_3") (pintype "passive"))
      (node (ref "U2") (pin "18") (pinfunction "RESET_18") (pintype "bidirectional"))
    )
    (net (code "60") (name "Net-(R4-Pad2)") (class "Default")
      (node (ref "R4") (pin "2") (pinfunction "2_2") (pintype "passive"))
      (node (ref "STA") (pin "+") (pinfunction "+_+") (pintype "passive"))
    )
    (net (code "61") (name "RESET") (class "Default")
      (node (ref "C19") (pin "2") (pinfunction "2_2") (pintype "passive"))
      (node (ref "CN2") (pin "10") (pinfunction "10_10") (pintype "passive"))
      (node (ref "IC2") (pin "40") (pinfunction "RESETN_40") (pintype "bidirectional"))
      (node (ref "J8") (pin "11") (pinfunction "11_11") (pintype "bidirectional"))
      (node (ref "R1") (pin "1") (pinfunction "1_1") (pintype "passive"))
      (node (ref "RESET") (pin "P$1") (pinfunction "1_P$1") (pintype "bidirectional"))
    )
    (net (code "62") (name "unconnected-(CN2-Pad6)") (class "Default")
      (node (ref "CN2") (pin "6") (pinfunction "6_6") (pintype "passive"))
    )
    (net (code "63") (name "unconnected-(CN2-Pad7)") (class "Default")
      (node (ref "CN2") (pin "7") (pinfunction "7_7") (pintype "passive"))
    )
    (net (code "64") (name "unconnected-(CN2-Pad8)") (class "Default")
      (node (ref "CN2") (pin "8") (pinfunction "8_8") (pintype "passive"))
    )
    (net (code "65") (name "unconnected-(D5-C5-Pad6)") (class "Default")
      (node (ref "D5") (pin "6") (pinfunction "C5_6") (pintype "passive"))
    )
    (net (code "66") (name "unconnected-(IC2-PA13{slash}I2C{slash}EIC{slash}SCOM2PAD1+{slash}TC2-Pad22)") (class "Default")
      (node (ref "IC2") (pin "22") (pinfunction "PA13/I2C/EIC/SCOM2PAD1+/TC2_22") (pintype "bidirectional"))
    )
    (net (code "67") (name "unconnected-(IC2-PA27{slash}EIC-Pad39)") (class "Default")
      (node (ref "IC2") (pin "39") (pinfunction "PA27/EIC_39") (pintype "bidirectional"))
    )
    (net (code "68") (name "unconnected-(IC2-PA28{slash}EIC-Pad41)") (class "Default")
      (node (ref "IC2") (pin "41") (pinfunction "PA28/EIC_41") (pintype "bidirectional"))
    )
    (net (code "69") (name "unconnected-(IC2-PB3{slash}EIC{slash}AIN11{slash}SCOM5PAD1-Pad48)") (class "Default")
      (node (ref "IC2") (pin "48") (pinfunction "PB3/EIC/AIN11/SCOM5PAD1_48") (pintype "bidirectional"))
    )
    (net (code "70") (name "unconnected-(IC2-PB22{slash}EIC{slash}SCOM5PAD2-Pad37)") (class "Default")
      (node (ref "IC2") (pin "37") (pinfunction "PB22/EIC/SCOM5PAD2_37") (pintype "bidirectional"))
    )
    (net (code "71") (name "unconnected-(IC2-PB23{slash}EIC{slash}SCOM5PAD3-Pad38)") (class "Default")
      (node (ref "IC2") (pin "38") (pinfunction "PB23/EIC/SCOM5PAD3_38") (pintype "bidirectional"))
    )
    (net (code "72") (name "unconnected-(J5-ID-Pad4)") (class "Default")
      (node (ref "J5") (pin "4") (pinfunction "ID_4") (pintype "bidirectional"))
    )
    (net (code "73") (name "unconnected-(J7-RSV{slash}D1-Pad8)") (class "Default")
      (node (ref "J7") (pin "8") (pinfunction "RSV/D1_8") (pintype "bidirectional"))
    )
    (net (code "74") (name "unconnected-(J7-RSV{slash}D2-Pad1)") (class "Default")
      (node (ref "J7") (pin "1") (pinfunction "RSV/D2_1") (pintype "bidirectional"))
    )
    (net (code "75") (name "unconnected-(SW1-PadCH1B)") (class "Default")
      (node (ref "SW1") (pin "CH1B") (pinfunction "CH1B_CH1B") (pintype "bidirectional"))
    )
    (net (code "76") (name "unconnected-(SW1-PadCH2B)") (class "Default")
      (node (ref "SW1") (pin "CH2B") (pinfunction "CH2B_CH2B") (pintype "bidirectional"))
    )
    (net (code "77") (name "unconnected-(U2-ADC0-Pad15)") (class "Default")
      (node (ref "U2") (pin "15") (pinfunction "ADC0_15") (pintype "bidirectional"))
    )
    (net (code "78") (name "unconnected-(U2-ADC1-Pad16)") (class "Default")
      (node (ref "U2") (pin "16") (pinfunction "ADC1_16") (pintype "bidirectional"))
    )
    (net (code "79") (name "unconnected-(U2-I2C2_SCL-Pad1)") (class "Default")
      (node (ref "U2") (pin "1") (pinfunction "I2C2_SCL_1") (pintype "bidirectional"))
    )
    (net (code "80") (name "unconnected-(U2-I2C2_SDA-Pad2)") (class "Default")
      (node (ref "U2") (pin "2") (pinfunction "I2C2_SDA_2") (pintype "bidirectional"))
    )
    (net (code "81") (name "unconnected-(U2-IO26-Pad25)") (class "Default")
      (node (ref "U2") (pin "25") (pinfunction "IO26_25") (pintype "bidirectional"))
    )
    (net (code "82") (name "unconnected-(U2-IO29-Pad24)") (class "Default")
      (node (ref "U2") (pin "24") (pinfunction "IO29_24") (pintype "bidirectional"))
    )
    (net (code "83") (name "unconnected-(U2-IO30-Pad31)") (class "Default")
      (node (ref "U2") (pin "31") (pinfunction "IO30_31") (pintype "bidirectional"))
    )
    (net (code "84") (name "unconnected-(U2-LCD_CS-Pad19)") (class "Default")
      (node (ref "U2") (pin "19") (pinfunction "LCD_CS_19") (pintype "bidirectional"))
    )
    (net (code "85") (name "unconnected-(U2-LCD_DIO-Pad21)") (class "Default")
      (node (ref "U2") (pin "21") (pinfunction "LCD_DIO_21") (pintype "bidirectional"))
    )
    (net (code "86") (name "unconnected-(U2-LCD_RST-Pad20)") (class "Default")
      (node (ref "U2") (pin "20") (pinfunction "LCD_RST_20") (pintype "bidirectional"))
    )
    (net (code "87") (name "unconnected-(U2-LCD_SCK-Pad23)") (class "Default")
      (node (ref "U2") (pin "23") (pinfunction "LCD_SCK_23") (pintype "bidirectional"))
    )
    (net (code "88") (name "unconnected-(U2-LCD_SDC-Pad22)") (class "Default")
      (node (ref "U2") (pin "22") (pinfunction "LCD_SDC_22") (pintype "bidirectional"))
    )
    (net (code "89") (name "unconnected-(U2-MIC_N-Pad33)") (class "Default")
      (node (ref "U2") (pin "33") (pinfunction "MIC_N_33") (pintype "bidirectional"))
    )
    (net (code "90") (name "unconnected-(U2-MIC_P-Pad34)") (class "Default")
      (node (ref "U2") (pin "34") (pinfunction "MIC_P_34") (pintype "bidirectional"))
    )
    (net (code "91") (name "unconnected-(U2-SD_CLK-Pad8)") (class "Default")
      (node (ref "U2") (pin "8") (pinfunction "SD_CLK_8") (pintype "bidirectional"))
    )
    (net (code "92") (name "unconnected-(U2-SD_CMD-Pad7)") (class "Default")
      (node (ref "U2") (pin "7") (pinfunction "SD_CMD_7") (pintype "bidirectional"))
    )
    (net (code "93") (name "unconnected-(U2-SD_D0-Pad6)") (class "Default")
      (node (ref "U2") (pin "6") (pinfunction "SD_D0_6") (pintype "bidirectional"))
    )
    (net (code "94") (name "unconnected-(U2-SD_D1-Pad5)") (class "Default")
      (node (ref "U2") (pin "5") (pinfunction "SD_D1_5") (pintype "bidirectional"))
    )
    (net (code "95") (name "unconnected-(U2-SD_D2-Pad4)") (class "Default")
      (node (ref "U2") (pin "4") (pinfunction "SD_D2_4") (pintype "bidirectional"))
    )
    (net (code "96") (name "unconnected-(U2-SD_D3-Pad3)") (class "Default")
      (node (ref "U2") (pin "3") (pinfunction "SD_D3_3") (pintype "bidirectional"))
    )
    (net (code "97") (name "unconnected-(U2-SPK_N-Pad14)") (class "Default")
      (node (ref "U2") (pin "14") (pinfunction "SPK_N_14") (pintype "bidirectional"))
    )
    (net (code "98") (name "unconnected-(U2-SPK_P-Pad13)") (class "Default")
      (node (ref "U2") (pin "13") (pinfunction "SPK_P_13") (pintype "bidirectional"))
    )
    (net (code "99") (name "unconnected-(U2-UART1_CTS-Pad52)") (class "Default")
      (node (ref "U2") (pin "52") (pinfunction "UART1_CTS_52") (pintype "bidirectional"))
    )
    (net (code "100") (name "unconnected-(U2-UART1_RTS-Pad51)") (class "Default")
      (node (ref "U2") (pin "51") (pinfunction "UART1_RTS_51") (pintype "bidirectional"))
    )
    (net (code "101") (name "unconnected-(U2-UART2_CTS-Pad48)") (class "Default")
      (node (ref "U2") (pin "48") (pinfunction "UART2_CTS_48") (pintype "bidirectional"))
    )
    (net (code "102") (name "unconnected-(U2-UART2_RTS-Pad47)") (class "Default")
      (node (ref "U2") (pin "47") (pinfunction "UART2_RTS_47") (pintype "bidirectional"))
    )
    (net (code "103") (name "unconnected-(U2-UART2_RXD-Pad49)") (class "Default")
      (node (ref "U2") (pin "49") (pinfunction "UART2_RXD_49") (pintype "bidirectional"))
    )
    (net (code "104") (name "unconnected-(U2-UART2_TXD-Pad50)") (class "Default")
      (node (ref "U2") (pin "50") (pinfunction "UART2_TXD_50") (pintype "bidirectional"))
    )
    (net (code "105") (name "unconnected-(U2-USB_N-Pad35)") (class "Default")
      (node (ref "U2") (pin "35") (pinfunction "USB_N_35") (pintype "bidirectional"))
    )
    (net (code "106") (name "unconnected-(U2-USB_P-Pad36)") (class "Default")
      (node (ref "U2") (pin "36") (pinfunction "USB_P_36") (pintype "bidirectional"))
    )
    (net (code "107") (name "unconnected-(U2-VUSB-Pad17)") (class "Default")
      (node (ref "U2") (pin "17") (pinfunction "VUSB_17") (pintype "bidirectional"))
    )
    (net (code "108") (name "unconnected-(U4-VPP-Pad6)") (class "Default")
      (node (ref "U4") (pin "6") (pinfunction "VPP_6") (pintype "bidirectional"))
    )
  )
)
